# 14pole.net
KiCad netlist of a schematic drawn in EAGLE
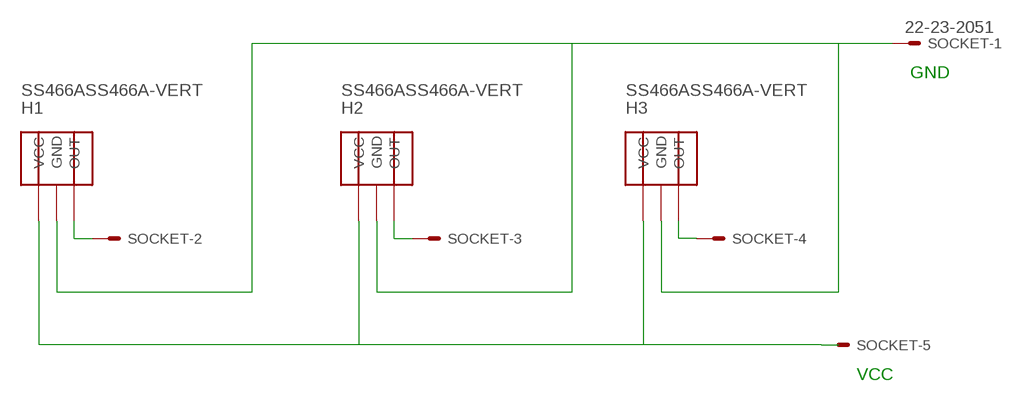
[diagram p0: schematic, sheet 1]

(export (version "E")
  (design (tool "Eeschema 10.0.6"))
  (components
    (comp (ref "H1")
      (value "SS466ASS466A-VERT")
      (footprint "eagle-import:SS466A")
      (libsource (lib "eagle-import") (part "SS466ASS466A-VERT"))
    )
    (comp (ref "H2")
      (value "SS466ASS466A-VERT")
      (footprint "eagle-import:SS466A")
      (libsource (lib "eagle-import") (part "SS466ASS466A-VERT"))
    )
    (comp (ref "H3")
      (value "SS466ASS466A-VERT")
      (footprint "eagle-import:SS466A")
      (libsource (lib "eagle-import") (part "SS466ASS466A-VERT"))
    )
    (comp (ref "SOCKET")
      (value "22-23-2051")
      (footprint "eagle-import:22-23-2051")
      (fields (field (name "MF") "MOLEX"))
      (libsource (lib "eagle-import") (part "22-23-2051"))
    )
  )
  (nets
    (net (code "1") (name "Net-(SOCKETA-S)") (class "Default")
      (node (ref "H1") (pin "GND") (pinfunction "GND_GND") (pintype "power_in"))
      (node (ref "H2") (pin "GND") (pinfunction "GND_GND") (pintype "power_in"))
      (node (ref "H3") (pin "GND") (pinfunction "GND_GND") (pintype "power_in"))
      (node (ref "SOCKET") (pin "1") (pinfunction "S_1") (pintype "passive"))
    )
    (net (code "2") (name "Net-(SOCKETB-S)") (class "Default")
      (node (ref "H1") (pin "OUT") (pinfunction "OUT_OUT") (pintype "output"))
      (node (ref "SOCKET") (pin "2") (pinfunction "S_2") (pintype "passive"))
    )
    (net (code "3") (name "Net-(SOCKETC-S)") (class "Default")
      (node (ref "H2") (pin "OUT") (pinfunction "OUT_OUT") (pintype "output"))
      (node (ref "SOCKET") (pin "3") (pinfunction "S_3") (pintype "passive"))
    )
    (net (code "4") (name "Net-(SOCKETD-S)") (class "Default")
      (node (ref "H3") (pin "OUT") (pinfunction "OUT_OUT") (pintype "output"))
      (node (ref "SOCKET") (pin "4") (pinfunction "S_4") (pintype "passive"))
    )
    (net (code "5") (name "Net-(SOCKETE-S)") (class "Default")
      (node (ref "H1") (pin "VCC") (pinfunction "VCC_VCC") (pintype "power_in"))
      (node (ref "H2") (pin "VCC") (pinfunction "VCC_VCC") (pintype "power_in"))
      (node (ref "H3") (pin "VCC") (pinfunction "VCC_VCC") (pintype "power_in"))
      (node (ref "SOCKET") (pin "5") (pinfunction "S_5") (pintype "passive"))
    )
  )
)
